# mLRS-rx-WioE5-E22-dual-v008.net
KiCad netlist of a schematic drawn in EAGLE
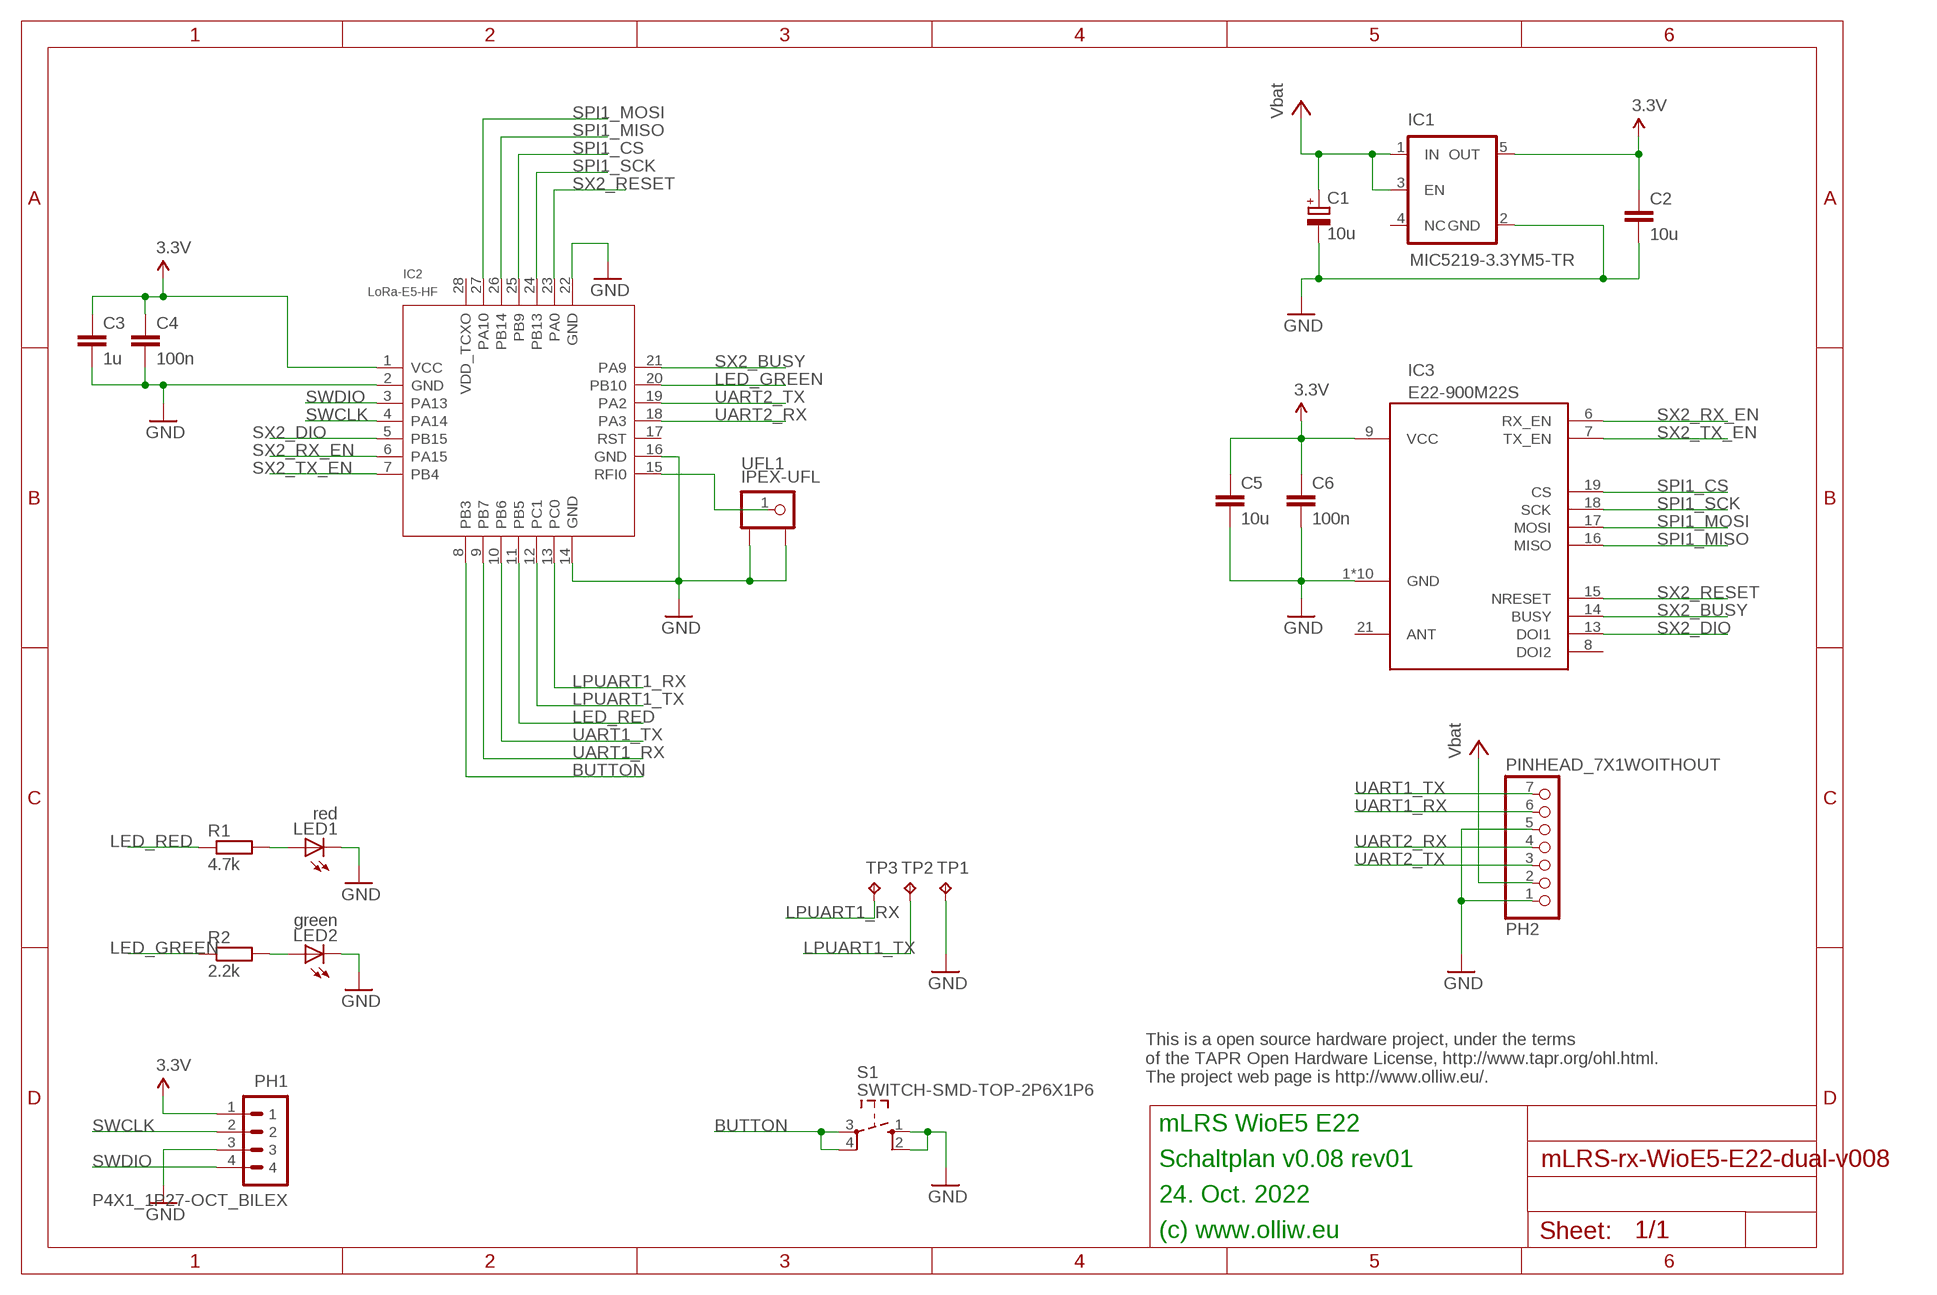
[diagram p0: schematic, sheet 1]

(export (version "E")
  (design (tool "Eeschema 10.0.6"))
  (components
    (comp (ref "C1")
      (value "10u")
      (footprint "eagle-import:SMC_A")
      (libsource (lib "eagle-import") (part "CPOL-EUSMCA"))
    )
    (comp (ref "C2")
      (value "10u")
      (footprint "eagle-import:C0805")
      (libsource (lib "eagle-import") (part "C-EUC0805"))
    )
    (comp (ref "C3")
      (value "1u")
      (footprint "eagle-import:C0603K")
      (libsource (lib "eagle-import") (part "C-EUC0603K"))
    )
    (comp (ref "C4")
      (value "100n")
      (footprint "eagle-import:C0402")
      (libsource (lib "eagle-import") (part "C-EUC0402"))
    )
    (comp (ref "C5")
      (value "10u")
      (footprint "eagle-import:C0805K")
      (libsource (lib "eagle-import") (part "C-EUC0805K"))
    )
    (comp (ref "C6")
      (value "100n")
      (footprint "eagle-import:C0402")
      (libsource (lib "eagle-import") (part "C-EUC0402"))
    )
    (comp (ref "IC1")
      (value "MIC5219-3.3YM5-TR")
      (footprint "eagle-import:SOT23-5")
      (libsource (lib "eagle-import") (part "V_REG_TPS76433SOT23-5"))
    )
    (comp (ref "IC2")
      (value "LoRa-E5-HF")
      (footprint "eagle-import:MOUDLE28P-1.25-12X12X2.5MM")
      (libsource (lib "eagle-import") (part "MOUDLE_LORA_E5"))
    )
    (comp (ref "IC3")
      (value "E22-900M22S")
      (footprint "eagle-import:E22-900M22S")
      (libsource (lib "eagle-import") (part "E22-900M22S"))
    )
    (comp (ref "LED1")
      (value "red")
      (footprint "eagle-import:CHIPLED_0603")
      (libsource (lib "eagle-import") (part "LEDCHIPLED_0603"))
    )
    (comp (ref "LED2")
      (value "green")
      (footprint "eagle-import:CHIPLED_0603")
      (libsource (lib "eagle-import") (part "LEDCHIPLED_0603"))
    )
    (comp (ref "PH1")
      (value "P4X1_1P27-OCT_BILEX")
      (footprint "eagle-import:4X1_1P27_OCT_BILEX")
      (libsource (lib "eagle-import") (part "P4X1_1P27-OCT_BILEX"))
    )
    (comp (ref "PH2")
      (value "PINHEAD_7X1WOITHOUT")
      (footprint "eagle-import:PINHEAD_7X1_WO")
      (libsource (lib "eagle-import") (part "PINHEAD_7X1WOITHOUT"))
    )
    (comp (ref "R1")
      (value "4.7k")
      (footprint "eagle-import:R0402")
      (libsource (lib "eagle-import") (part "R-EU_R0402"))
    )
    (comp (ref "R2")
      (value "2.2k")
      (footprint "eagle-import:R0402")
      (libsource (lib "eagle-import") (part "R-EU_R0402"))
    )
    (comp (ref "S1")
      (value "SWITCH-SMD-TOP-2P6X1P6")
      (footprint "eagle-import:TACTILE-SWITCH-SMD-TOP-2P6X1X6")
      (libsource (lib "eagle-import") (part "SWITCH-SMD-TOP-2P6X1P6"))
    )
    (comp (ref "TP1")
      (value "TPB1,27")
      (footprint "eagle-import:B1,27")
      (libsource (lib "eagle-import") (part "TPB1,27"))
    )
    (comp (ref "TP2")
      (value "TPB1,27")
      (footprint "eagle-import:B1,27")
      (libsource (lib "eagle-import") (part "TPB1,27"))
    )
    (comp (ref "TP3")
      (value "TPB1,27")
      (footprint "eagle-import:B1,27")
      (libsource (lib "eagle-import") (part "TPB1,27"))
    )
    (comp (ref "UFL1")
      (value "IPEX-UFL")
      (footprint "eagle-import:IPEX-UFL-SMD")
      (libsource (lib "eagle-import") (part "IPEX-UFL"))
    )
  )
  (nets
    (net (code "1") (name "/BUTTON") (class "Default")
      (node (ref "IC2") (pin "8") (pinfunction "PB3_8") (pintype "bidirectional"))
      (node (ref "S1") (pin "3") (pinfunction "3_3") (pintype "passive"))
      (node (ref "S1") (pin "4") (pinfunction "4_4") (pintype "passive"))
    )
    (net (code "2") (name "/LED_GREEN") (class "Default")
      (node (ref "IC2") (pin "20") (pinfunction "PB10_20") (pintype "bidirectional"))
      (node (ref "R2") (pin "1") (pinfunction "1_1") (pintype "passive"))
    )
    (net (code "3") (name "/LED_RED") (class "Default")
      (node (ref "IC2") (pin "11") (pinfunction "PB5_11") (pintype "bidirectional"))
      (node (ref "R1") (pin "1") (pinfunction "1_1") (pintype "passive"))
    )
    (net (code "4") (name "/LPUART1_RX") (class "Default")
      (node (ref "IC2") (pin "13") (pinfunction "PC0_13") (pintype "bidirectional"))
      (node (ref "TP3") (pin "TP") (pinfunction "TP_TP") (pintype "input"))
    )
    (net (code "5") (name "/LPUART1_TX") (class "Default")
      (node (ref "IC2") (pin "12") (pinfunction "PC1_12") (pintype "bidirectional"))
      (node (ref "TP2") (pin "TP") (pinfunction "TP_TP") (pintype "input"))
    )
    (net (code "6") (name "/SPI1_CS") (class "Default")
      (node (ref "IC2") (pin "25") (pinfunction "PB9_25") (pintype "bidirectional"))
      (node (ref "IC3") (pin "19") (pinfunction "CS_19") (pintype "bidirectional"))
    )
    (net (code "7") (name "/SPI1_MISO") (class "Default")
      (node (ref "IC2") (pin "26") (pinfunction "PB14_26") (pintype "bidirectional"))
      (node (ref "IC3") (pin "16") (pinfunction "MISO_16") (pintype "bidirectional"))
    )
    (net (code "8") (name "/SPI1_MOSI") (class "Default")
      (node (ref "IC2") (pin "27") (pinfunction "PA10_27") (pintype "bidirectional"))
      (node (ref "IC3") (pin "17") (pinfunction "MOSI_17") (pintype "bidirectional"))
    )
    (net (code "9") (name "/SPI1_SCK") (class "Default")
      (node (ref "IC2") (pin "24") (pinfunction "PB13_24") (pintype "bidirectional"))
      (node (ref "IC3") (pin "18") (pinfunction "SCK_18") (pintype "bidirectional"))
    )
    (net (code "10") (name "/SWCLK") (class "Default")
      (node (ref "IC2") (pin "4") (pinfunction "PA14_4") (pintype "bidirectional"))
      (node (ref "PH1") (pin "2") (pinfunction "2_2") (pintype "passive"))
    )
    (net (code "11") (name "/SWDIO") (class "Default")
      (node (ref "IC2") (pin "3") (pinfunction "PA13_3") (pintype "bidirectional"))
      (node (ref "PH1") (pin "4") (pinfunction "4_4") (pintype "passive"))
    )
    (net (code "12") (name "/SX2_BUSY") (class "Default")
      (node (ref "IC2") (pin "21") (pinfunction "PA9_21") (pintype "bidirectional"))
      (node (ref "IC3") (pin "14") (pinfunction "BUSY_14") (pintype "bidirectional"))
    )
    (net (code "13") (name "/SX2_DIO") (class "Default")
      (node (ref "IC2") (pin "5") (pinfunction "PB15_5") (pintype "bidirectional"))
      (node (ref "IC3") (pin "13") (pinfunction "DOI1_13") (pintype "bidirectional"))
    )
    (net (code "14") (name "/SX2_RESET") (class "Default")
      (node (ref "IC2") (pin "23") (pinfunction "PA0_23") (pintype "bidirectional"))
      (node (ref "IC3") (pin "15") (pinfunction "NRESET_15") (pintype "input"))
    )
    (net (code "15") (name "/SX2_RX_EN") (class "Default")
      (node (ref "IC2") (pin "6") (pinfunction "PA15_6") (pintype "bidirectional"))
      (node (ref "IC3") (pin "6") (pinfunction "RX_EN_6") (pintype "bidirectional"))
    )
    (net (code "16") (name "/SX2_TX_EN") (class "Default")
      (node (ref "IC2") (pin "7") (pinfunction "PB4_7") (pintype "bidirectional"))
      (node (ref "IC3") (pin "7") (pinfunction "TX_EN_7") (pintype "bidirectional"))
    )
    (net (code "17") (name "/UART1_RX") (class "Default")
      (node (ref "IC2") (pin "9") (pinfunction "PB7_9") (pintype "bidirectional"))
      (node (ref "PH2") (pin "6") (pinfunction "6_6") (pintype "passive"))
    )
    (net (code "18") (name "/UART1_TX") (class "Default")
      (node (ref "IC2") (pin "10") (pinfunction "PB6_10") (pintype "bidirectional"))
      (node (ref "PH2") (pin "7") (pinfunction "7_7") (pintype "passive"))
    )
    (net (code "19") (name "/UART2_RX") (class "Default")
      (node (ref "IC2") (pin "18") (pinfunction "PA3_18") (pintype "bidirectional"))
      (node (ref "PH2") (pin "4") (pinfunction "4_4") (pintype "passive"))
    )
    (net (code "20") (name "/UART2_TX") (class "Default")
      (node (ref "IC2") (pin "19") (pinfunction "PA2_19") (pintype "bidirectional"))
      (node (ref "PH2") (pin "3") (pinfunction "3_3") (pintype "passive"))
    )
    (net (code "21") (name "3.3V") (class "Default")
      (node (ref "C2") (pin "1") (pinfunction "1_1") (pintype "passive"))
      (node (ref "C3") (pin "1") (pinfunction "1_1") (pintype "passive"))
      (node (ref "C4") (pin "1") (pinfunction "1_1") (pintype "passive"))
      (node (ref "C5") (pin "1") (pinfunction "1_1") (pintype "passive"))
      (node (ref "C6") (pin "1") (pinfunction "1_1") (pintype "passive"))
      (node (ref "IC1") (pin "5") (pinfunction "OUT_5") (pintype "output"))
      (node (ref "IC2") (pin "1") (pinfunction "VCC_1") (pintype "bidirectional"))
      (node (ref "IC3") (pin "9") (pinfunction "VCC_9") (pintype "power_in"))
      (node (ref "PH1") (pin "1") (pinfunction "1_1") (pintype "passive"))
    )
    (net (code "22") (name "GND") (class "Default")
      (node (ref "C1") (pin "-") (pinfunction "-_-") (pintype "passive"))
      (node (ref "C2") (pin "2") (pinfunction "2_2") (pintype "passive"))
      (node (ref "C3") (pin "2") (pinfunction "2_2") (pintype "passive"))
      (node (ref "C4") (pin "2") (pinfunction "2_2") (pintype "passive"))
      (node (ref "C5") (pin "2") (pinfunction "2_2") (pintype "passive"))
      (node (ref "C6") (pin "2") (pinfunction "2_2") (pintype "passive"))
      (node (ref "IC1") (pin "2") (pinfunction "GND_2") (pintype "power_in"))
      (node (ref "IC2") (pin "14") (pinfunction "GND_14") (pintype "bidirectional"))
      (node (ref "IC2") (pin "16") (pinfunction "GND_16") (pintype "bidirectional"))
      (node (ref "IC2") (pin "2") (pinfunction "GND_2") (pintype "bidirectional"))
      (node (ref "IC2") (pin "22") (pinfunction "GND_22") (pintype "bidirectional"))
      (node (ref "IC3") (pin "1") (pinfunction "GND_1") (pintype "power_in"))
      (node (ref "IC3") (pin "10") (pinfunction "GND_10") (pintype "power_in"))
      (node (ref "IC3") (pin "11") (pinfunction "GND_11") (pintype "power_in"))
      (node (ref "IC3") (pin "12") (pinfunction "GND_12") (pintype "power_in"))
      (node (ref "IC3") (pin "2") (pinfunction "GND_2") (pintype "power_in"))
      (node (ref "IC3") (pin "20") (pinfunction "GND_20") (pintype "power_in"))
      (node (ref "IC3") (pin "22") (pinfunction "GND_22") (pintype "power_in"))
      (node (ref "IC3") (pin "3") (pinfunction "GND_3") (pintype "power_in"))
      (node (ref "IC3") (pin "4") (pinfunction "GND_4") (pintype "power_in"))
      (node (ref "IC3") (pin "5") (pinfunction "GND_5") (pintype "power_in"))
      (node (ref "LED1") (pin "C") (pinfunction "C_C") (pintype "passive"))
      (node (ref "LED2") (pin "C") (pinfunction "C_C") (pintype "passive"))
      (node (ref "PH1") (pin "3") (pinfunction "3_3") (pintype "passive"))
      (node (ref "PH2") (pin "1") (pinfunction "1_1") (pintype "passive"))
      (node (ref "PH2") (pin "5") (pinfunction "5_5") (pintype "passive"))
      (node (ref "S1") (pin "1") (pinfunction "1_1") (pintype "passive"))
      (node (ref "S1") (pin "2") (pinfunction "2_2") (pintype "passive"))
      (node (ref "TP1") (pin "TP") (pinfunction "TP_TP") (pintype "input"))
      (node (ref "UFL1") (pin "2") (pinfunction "2_2") (pintype "power_in"))
      (node (ref "UFL1") (pin "3") (pinfunction "3_3") (pintype "power_in"))
    )
    (net (code "23") (name "Net-(IC2-RFI0)") (class "Default")
      (node (ref "IC2") (pin "15") (pinfunction "RFI0_15") (pintype "bidirectional"))
      (node (ref "UFL1") (pin "1") (pinfunction "1_1") (pintype "passive"))
    )
    (net (code "24") (name "Net-(LED1-PadA)") (class "Default")
      (node (ref "LED1") (pin "A") (pinfunction "A_A") (pintype "passive"))
      (node (ref "R1") (pin "2") (pinfunction "2_2") (pintype "passive"))
    )
    (net (code "25") (name "Net-(LED2-PadA)") (class "Default")
      (node (ref "LED2") (pin "A") (pinfunction "A_A") (pintype "passive"))
      (node (ref "R2") (pin "2") (pinfunction "2_2") (pintype "passive"))
    )
    (net (code "26") (name "Vbat") (class "Default")
      (node (ref "C1") (pin "+") (pinfunction "+_+") (pintype "passive"))
      (node (ref "IC1") (pin "1") (pinfunction "IN_1") (pintype "power_in"))
      (node (ref "IC1") (pin "3") (pinfunction "EN_3") (pintype "input"))
      (node (ref "PH2") (pin "2") (pinfunction "2_2") (pintype "passive"))
    )
    (net (code "27") (name "unconnected-(IC1-NC-Pad4)") (class "Default")
      (node (ref "IC1") (pin "4") (pinfunction "NC_4") (pintype "passive"))
    )
    (net (code "28") (name "unconnected-(IC2-RST-Pad17)") (class "Default")
      (node (ref "IC2") (pin "17") (pinfunction "RST_17") (pintype "bidirectional"))
    )
    (net (code "29") (name "unconnected-(IC2-VDD_TCXO-Pad28)") (class "Default")
      (node (ref "IC2") (pin "28") (pinfunction "VDD_TCXO_28") (pintype "bidirectional"))
    )
    (net (code "30") (name "unconnected-(IC3-ANT-Pad21)") (class "Default")
      (node (ref "IC3") (pin "21") (pinfunction "ANT_21") (pintype "bidirectional"))
    )
    (net (code "31") (name "unconnected-(IC3-DOI2-Pad8)") (class "Default")
      (node (ref "IC3") (pin "8") (pinfunction "DOI2_8") (pintype "bidirectional"))
    )
  )
)
